# piezo-buffer-and-preamp-ritter_V0-3-thru.net
KiCad netlist of a schematic drawn in EAGLE
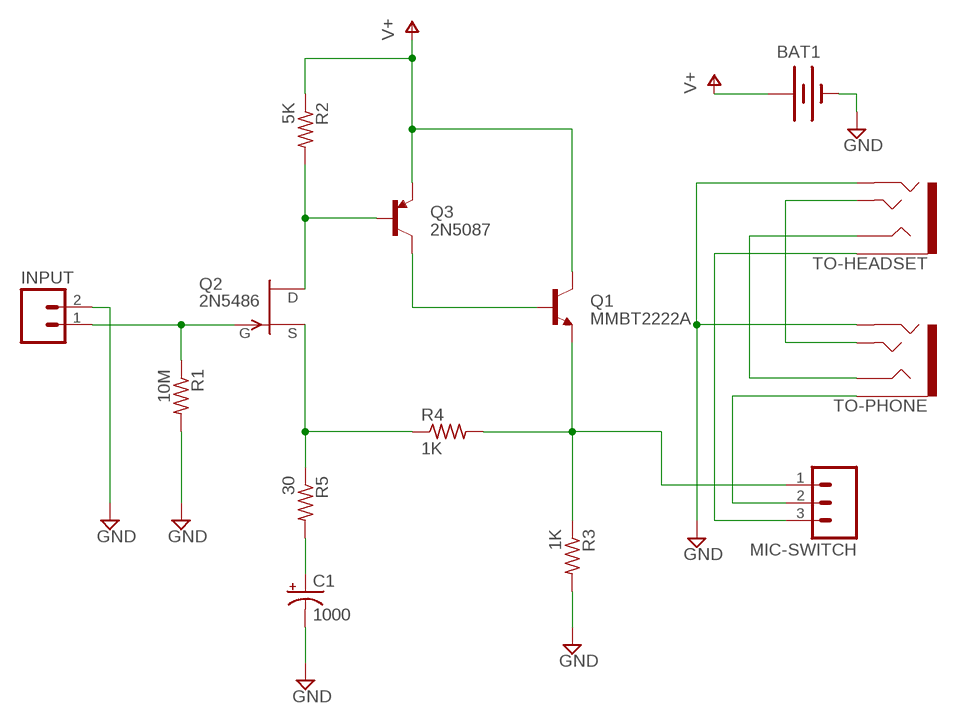
[diagram p0: schematic, sheet 1]

(export (version "E")
  (design (tool "Eeschema 10.0.6"))
  (components
    (comp (ref "BAT1")
      (value "BATTERYAAA-KIT")
      (footprint "eagle-import:BATTERY-AAA-KIT")
      (libsource (lib "eagle-import") (part "BATTERYAAA-KIT"))
    )
    (comp (ref "C1")
      (value "1000")
      (footprint "eagle-import:CPOL-RADIAL-1000UF-25V")
      (libsource (lib "eagle-import") (part "CAP_POLPTH4"))
    )
    (comp (ref "INPUT")
      (value "M02LOCK")
      (footprint "eagle-import:1X02_LOCK")
      (libsource (lib "eagle-import") (part "M02LOCK"))
    )
    (comp (ref "MIC-SWITCH")
      (value "M03LOCK")
      (footprint "eagle-import:1X03_LOCK")
      (libsource (lib "eagle-import") (part "M03LOCK"))
    )
    (comp (ref "Q1")
      (value "MMBT2222A")
      (footprint "eagle-import:TO-92")
      (libsource (lib "eagle-import") (part "TRANSISTOR_NPNTO92"))
    )
    (comp (ref "Q2")
      (value "2N5486")
      (footprint "eagle-import:TO92-")
      (libsource (lib "eagle-import") (part "?5482N6"))
    )
    (comp (ref "Q3")
      (value "2N5087")
      (footprint "eagle-import:TO-92")
      (libsource (lib "eagle-import") (part "TRANSISTOR_PNPTO92"))
    )
    (comp (ref "R1")
      (value "10M")
      (footprint "eagle-import:V526-0")
      (libsource (lib "eagle-import") (part "R-US_V526-0"))
    )
    (comp (ref "R2")
      (value "5K")
      (footprint "eagle-import:V526-0")
      (libsource (lib "eagle-import") (part "R-US_V526-0"))
    )
    (comp (ref "R3")
      (value "1K")
      (footprint "eagle-import:V526-0")
      (libsource (lib "eagle-import") (part "R-US_V526-0"))
    )
    (comp (ref "R4")
      (value "1K")
      (footprint "eagle-import:V526-0")
      (libsource (lib "eagle-import") (part "R-US_V526-0"))
    )
    (comp (ref "R5")
      (value "30")
      (footprint "eagle-import:V526-0")
      (libsource (lib "eagle-import") (part "R-US_V526-0"))
    )
    (comp (ref "TO-HEADSET")
      (value "AUDIO-JACK3")
      (footprint "eagle-import:AUDIO-JACK-TRRS-SMD")
      (libsource (lib "eagle-import") (part "AUDIO-JACK3"))
    )
    (comp (ref "TO-PHONE")
      (value "AUDIO-JACK3")
      (footprint "eagle-import:AUDIO-JACK-TRRS-SMD")
      (libsource (lib "eagle-import") (part "AUDIO-JACK3"))
    )
  )
  (nets
    (net (code "1") (name "GND") (class "Default")
      (node (ref "BAT1") (pin "GND@1") (pinfunction "-_GND@1") (pintype "power_in"))
      (node (ref "C1") (pin "-") (pinfunction "-_-") (pintype "passive"))
      (node (ref "INPUT") (pin "2") (pinfunction "2_2") (pintype "passive"))
      (node (ref "R1") (pin "2") (pinfunction "2_2") (pintype "passive"))
      (node (ref "R3") (pin "2") (pinfunction "2_2") (pintype "passive"))
      (node (ref "TO-HEADSET") (pin "RING2") (pinfunction "RING2_RING2") (pintype "bidirectional"))
      (node (ref "TO-PHONE") (pin "RING2") (pinfunction "RING2_RING2") (pintype "bidirectional"))
    )
    (net (code "2") (name "Net-(C1-Pad+)") (class "Default")
      (node (ref "C1") (pin "+") (pinfunction "+_+") (pintype "passive"))
      (node (ref "R5") (pin "2") (pinfunction "2_2") (pintype "passive"))
    )
    (net (code "3") (name "Net-(MIC-SWITCH-Pad2)") (class "Default")
      (node (ref "MIC-SWITCH") (pin "2") (pinfunction "2_2") (pintype "passive"))
      (node (ref "TO-PHONE") (pin "EARTH") (pinfunction "EARTH_EARTH") (pintype "bidirectional"))
    )
    (net (code "4") (name "Net-(MIC-SWITCH-Pad3)") (class "Default")
      (node (ref "MIC-SWITCH") (pin "3") (pinfunction "3_3") (pintype "passive"))
      (node (ref "TO-HEADSET") (pin "EARTH") (pinfunction "EARTH_EARTH") (pintype "bidirectional"))
    )
    (net (code "5") (name "Net-(Q1-B)") (class "Default")
      (node (ref "Q1") (pin "2") (pinfunction "B_2") (pintype "passive"))
      (node (ref "Q3") (pin "3") (pinfunction "C_3") (pintype "passive"))
    )
    (net (code "6") (name "Net-(Q1-E)") (class "Default")
      (node (ref "MIC-SWITCH") (pin "1") (pinfunction "1_1") (pintype "passive"))
      (node (ref "Q1") (pin "1") (pinfunction "E_1") (pintype "passive"))
      (node (ref "R3") (pin "1") (pinfunction "1_1") (pintype "passive"))
      (node (ref "R4") (pin "2") (pinfunction "2_2") (pintype "passive"))
    )
    (net (code "7") (name "Net-(Q2-D)") (class "Default")
      (node (ref "Q2") (pin "3") (pinfunction "D_3") (pintype "passive"))
      (node (ref "Q3") (pin "2") (pinfunction "B_2") (pintype "passive"))
      (node (ref "R2") (pin "2") (pinfunction "2_2") (pintype "passive"))
    )
    (net (code "8") (name "Net-(Q2-G)") (class "Default")
      (node (ref "INPUT") (pin "1") (pinfunction "1_1") (pintype "passive"))
      (node (ref "Q2") (pin "1") (pinfunction "G_1") (pintype "passive"))
      (node (ref "R1") (pin "1") (pinfunction "1_1") (pintype "passive"))
    )
    (net (code "9") (name "Net-(Q2-S)") (class "Default")
      (node (ref "Q2") (pin "2") (pinfunction "S_2") (pintype "passive"))
      (node (ref "R4") (pin "1") (pinfunction "1_1") (pintype "passive"))
      (node (ref "R5") (pin "1") (pinfunction "1_1") (pintype "passive"))
    )
    (net (code "10") (name "Net-(TO-HEADSET-PadRING1)") (class "Default")
      (node (ref "TO-HEADSET") (pin "RING1") (pinfunction "RING1_RING1") (pintype "bidirectional"))
      (node (ref "TO-PHONE") (pin "RING1") (pinfunction "RING1_RING1") (pintype "bidirectional"))
    )
    (net (code "11") (name "Net-(TO-HEADSET-PadTIP)") (class "Default")
      (node (ref "TO-HEADSET") (pin "TIP") (pinfunction "TIP_TIP") (pintype "bidirectional"))
      (node (ref "TO-PHONE") (pin "TIP") (pinfunction "TIP_TIP") (pintype "bidirectional"))
    )
    (net (code "12") (name "V+") (class "Default")
      (node (ref "BAT1") (pin "PWR@1") (pinfunction "+_PWR@1") (pintype "power_in"))
      (node (ref "Q1") (pin "3") (pinfunction "C_3") (pintype "passive"))
      (node (ref "Q3") (pin "1") (pinfunction "E_1") (pintype "passive"))
      (node (ref "R2") (pin "1") (pinfunction "1_1") (pintype "passive"))
    )
  )
)
